# mcu-adc.net
KiCad netlist of a schematic drawn in Altium Designer
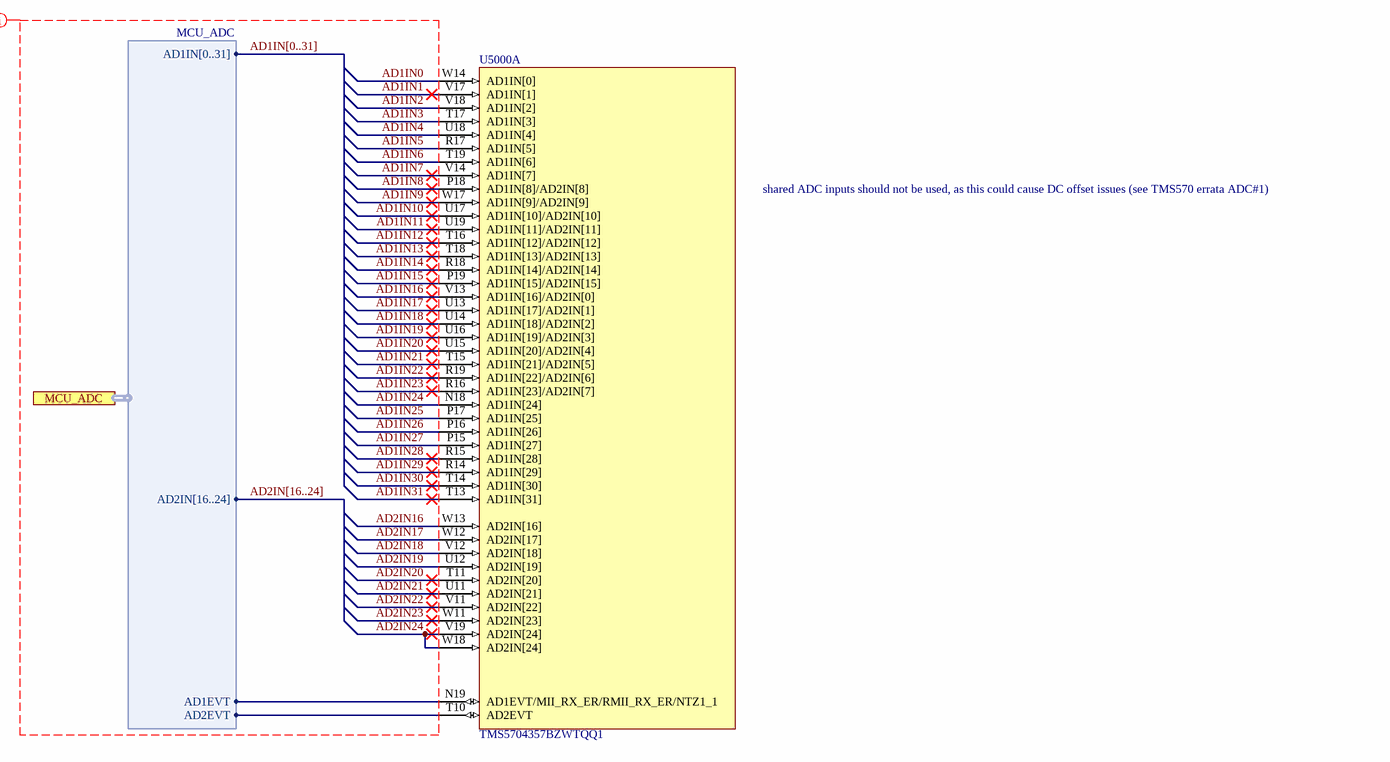
[diagram p0: mcu-adc.SchDoc]

(export (version "E")
  (design (tool "Eeschema 10.0.6"))
  (components
    (comp (ref "U5000")
      (value "TMS5704357BZWTQQ1")
      (footprint "BGA337C80P19X19_1600X1600X140")
      (libsource (lib "TMS570LC4357") (part "TMS5704357BZWTQQ1"))
    )
  )
  (nets
    (net (code "2") (name "/AD1EVT") (class "Default")
      (node (ref "U5000") (pin "N19") (pinfunction "AD1EVT/MII_RX_ER/RMII_RX_ER/NTZ1_1_N19") (pintype "bidirectional"))
    )
    (net (code "3") (name "/AD1IN0") (class "Default")
      (node (ref "U5000") (pin "W14") (pinfunction "AD1IN[0]_W14") (pintype "input"))
    )
    (net (code "4") (name "/AD1IN1") (class "Default")
      (node (ref "U5000") (pin "V17") (pinfunction "AD1IN[1]_V17") (pintype "input"))
    )
    (net (code "5") (name "/AD1IN2") (class "Default")
      (node (ref "U5000") (pin "V18") (pinfunction "AD1IN[2]_V18") (pintype "input"))
    )
    (net (code "6") (name "/AD1IN3") (class "Default")
      (node (ref "U5000") (pin "T17") (pinfunction "AD1IN[3]_T17") (pintype "input"))
    )
    (net (code "7") (name "/AD1IN4") (class "Default")
      (node (ref "U5000") (pin "U18") (pinfunction "AD1IN[4]_U18") (pintype "input"))
    )
    (net (code "8") (name "/AD1IN5") (class "Default")
      (node (ref "U5000") (pin "R17") (pinfunction "AD1IN[5]_R17") (pintype "input"))
    )
    (net (code "9") (name "/AD1IN6") (class "Default")
      (node (ref "U5000") (pin "T19") (pinfunction "AD1IN[6]_T19") (pintype "input"))
    )
    (net (code "10") (name "/AD1IN7") (class "Default")
      (node (ref "U5000") (pin "V14") (pinfunction "AD1IN[7]_V14") (pintype "input"))
    )
    (net (code "11") (name "/AD1IN8") (class "Default")
      (node (ref "U5000") (pin "P18") (pinfunction "AD1IN[8]/AD2IN[8]_P18") (pintype "input"))
    )
    (net (code "12") (name "/AD1IN9") (class "Default")
      (node (ref "U5000") (pin "W17") (pinfunction "AD1IN[9]/AD2IN[9]_W17") (pintype "input"))
    )
    (net (code "13") (name "/AD1IN10") (class "Default")
      (node (ref "U5000") (pin "U17") (pinfunction "AD1IN[10]/AD2IN[10]_U17") (pintype "input"))
    )
    (net (code "14") (name "/AD1IN11") (class "Default")
      (node (ref "U5000") (pin "U19") (pinfunction "AD1IN[11]/AD2IN[11]_U19") (pintype "input"))
    )
    (net (code "15") (name "/AD1IN12") (class "Default")
      (node (ref "U5000") (pin "T16") (pinfunction "AD1IN[12]/AD2IN[12]_T16") (pintype "input"))
    )
    (net (code "16") (name "/AD1IN13") (class "Default")
      (node (ref "U5000") (pin "T18") (pinfunction "AD1IN[13]/AD2IN[13]_T18") (pintype "input"))
    )
    (net (code "17") (name "/AD1IN14") (class "Default")
      (node (ref "U5000") (pin "R18") (pinfunction "AD1IN[14]/AD2IN[14]_R18") (pintype "input"))
    )
    (net (code "18") (name "/AD1IN15") (class "Default")
      (node (ref "U5000") (pin "P19") (pinfunction "AD1IN[15]/AD2IN[15]_P19") (pintype "input"))
    )
    (net (code "19") (name "/AD1IN16") (class "Default")
      (node (ref "U5000") (pin "V13") (pinfunction "AD1IN[16]/AD2IN[0]_V13") (pintype "input"))
    )
    (net (code "20") (name "/AD1IN17") (class "Default")
      (node (ref "U5000") (pin "U13") (pinfunction "AD1IN[17]/AD2IN[1]_U13") (pintype "input"))
    )
    (net (code "21") (name "/AD1IN18") (class "Default")
      (node (ref "U5000") (pin "U14") (pinfunction "AD1IN[18]/AD2IN[2]_U14") (pintype "input"))
    )
    (net (code "22") (name "/AD1IN19") (class "Default")
      (node (ref "U5000") (pin "U16") (pinfunction "AD1IN[19]/AD2IN[3]_U16") (pintype "input"))
    )
    (net (code "23") (name "/AD1IN20") (class "Default")
      (node (ref "U5000") (pin "U15") (pinfunction "AD1IN[20]/AD2IN[4]_U15") (pintype "input"))
    )
    (net (code "24") (name "/AD1IN21") (class "Default")
      (node (ref "U5000") (pin "T15") (pinfunction "AD1IN[21]/AD2IN[5]_T15") (pintype "input"))
    )
    (net (code "25") (name "/AD1IN22") (class "Default")
      (node (ref "U5000") (pin "R19") (pinfunction "AD1IN[22]/AD2IN[6]_R19") (pintype "input"))
    )
    (net (code "26") (name "/AD1IN23") (class "Default")
      (node (ref "U5000") (pin "R16") (pinfunction "AD1IN[23]/AD2IN[7]_R16") (pintype "input"))
    )
    (net (code "27") (name "/AD1IN24") (class "Default")
      (node (ref "U5000") (pin "N18") (pinfunction "AD1IN[24]_N18") (pintype "input"))
    )
    (net (code "28") (name "/AD1IN25") (class "Default")
      (node (ref "U5000") (pin "P17") (pinfunction "AD1IN[25]_P17") (pintype "input"))
    )
    (net (code "29") (name "/AD1IN26") (class "Default")
      (node (ref "U5000") (pin "P16") (pinfunction "AD1IN[26]_P16") (pintype "input"))
    )
    (net (code "30") (name "/AD1IN27") (class "Default")
      (node (ref "U5000") (pin "P15") (pinfunction "AD1IN[27]_P15") (pintype "input"))
    )
    (net (code "31") (name "/AD1IN28") (class "Default")
      (node (ref "U5000") (pin "R15") (pinfunction "AD1IN[28]_R15") (pintype "input"))
    )
    (net (code "32") (name "/AD1IN29") (class "Default")
      (node (ref "U5000") (pin "R14") (pinfunction "AD1IN[29]_R14") (pintype "input"))
    )
    (net (code "33") (name "/AD1IN30") (class "Default")
      (node (ref "U5000") (pin "T14") (pinfunction "AD1IN[30]_T14") (pintype "input"))
    )
    (net (code "34") (name "/AD1IN31") (class "Default")
      (node (ref "U5000") (pin "T13") (pinfunction "AD1IN[31]_T13") (pintype "input"))
    )
    (net (code "36") (name "/AD2EVT") (class "Default")
      (node (ref "U5000") (pin "T10") (pinfunction "AD2EVT_T10") (pintype "bidirectional"))
    )
    (net (code "37") (name "/AD2IN16") (class "Default")
      (node (ref "U5000") (pin "W13") (pinfunction "AD2IN[16]_W13") (pintype "input"))
    )
    (net (code "38") (name "/AD2IN17") (class "Default")
      (node (ref "U5000") (pin "W12") (pinfunction "AD2IN[17]_W12") (pintype "input"))
    )
    (net (code "39") (name "/AD2IN18") (class "Default")
      (node (ref "U5000") (pin "V12") (pinfunction "AD2IN[18]_V12") (pintype "input"))
    )
    (net (code "40") (name "/AD2IN19") (class "Default")
      (node (ref "U5000") (pin "U12") (pinfunction "AD2IN[19]_U12") (pintype "input"))
    )
    (net (code "41") (name "/AD2IN20") (class "Default")
      (node (ref "U5000") (pin "T11") (pinfunction "AD2IN[20]_T11") (pintype "input"))
    )
    (net (code "42") (name "/AD2IN21") (class "Default")
      (node (ref "U5000") (pin "U11") (pinfunction "AD2IN[21]_U11") (pintype "input"))
    )
    (net (code "43") (name "/AD2IN22") (class "Default")
      (node (ref "U5000") (pin "V11") (pinfunction "AD2IN[22]_V11") (pintype "input"))
    )
    (net (code "44") (name "/AD2IN23") (class "Default")
      (node (ref "U5000") (pin "W11") (pinfunction "AD2IN[23]_W11") (pintype "input"))
    )
    (net (code "45") (name "/AD2IN24") (class "Default")
      (node (ref "U5000") (pin "V19") (pinfunction "AD2IN[24]_V19") (pintype "input"))
      (node (ref "U5000") (pin "W18") (pinfunction "AD2IN[24]_W18") (pintype "input"))
    )
  )
)
